# Relay.net
KiCad netlist of a schematic drawn in Altium Designer
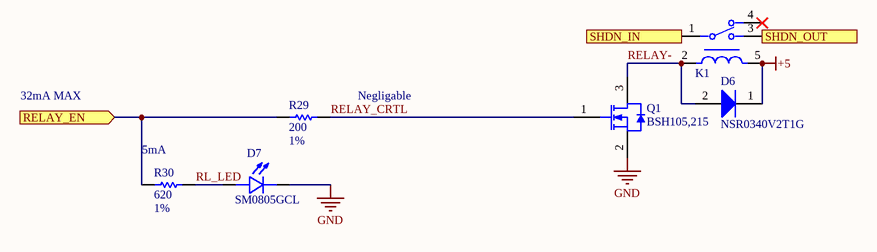
[diagram p0: Relay.SchDoc]

(export (version "E")
  (design (tool "Eeschema 10.0.6"))
  (components
    (comp (ref "D6")
      (value "NSR0340V2T1G")
      (footprint "ONSC-SOD-523-2-502-01_V")
      (description "Schottky Barrier Diode, 2-Pin SOD-523, Pb-Free, Tape and Reel")
      (fields (field (name "MANUFACTURER") "On Semiconductor"))
      (libsource (lib "Altium Content Vault") (part "ONSC-D-K1A2-2"))
    )
    (comp (ref "D7")
      (value "SM0805GCL")
      (footprint "LEDC2012X135N_SM0805GCL(Primary)")
      (description "Green 574nm LED Indication - Discrete 1.9V 0805 (2012 Metric)")
      (libsource (lib "bspd parts") (part "SM0805GCL"))
    )
    (comp (ref "K1")
      (value "Relay_Omron_Electronics_Inc._G5LE-1_DC5_eec")
      (footprint "Omron_Electronics_Inc._G5LE-1_DC5_0")
      (description "RELAY GEN PURPOSE SPDT 10A 5V")
      (fields (field (name "PART NUMBER") "G5LE-1 DC5") (field (name "VOLTAGE") "30V"))
      (libsource (lib "bspd parts") (part "Relay_Omron_Electronics_Inc._G5LE-1_DC5_eec"))
    )
    (comp (ref "Q1")
      (value "BSH105,215")
      (footprint "NXP-SOT23_M")
      (fields (field (name "MANUFACTURER") "NXP Semiconductors"))
      (libsource (lib "Altium Content Vault") (part "NXP-NMOS-GSD-3_B"))
    )
    (comp (ref "R29")
      (value "RES 0603 200 1%")
      (footprint "0603_RES")
      (description "Resistor Surface Mount, 200 Ohms, 0603 Footprint, 1% Tolerance 0.1W")
      (fields
        (field (name "VAL") "200")
        (field (name "TOL") "1%")
        (field (name "MANUFACTURER") "Various")
        (field (name "TOLERANCE") "1%")
      )
      (libsource (lib "Passive Components") (part "res"))
    )
    (comp (ref "R30")
      (value "RES 0603 620 1%")
      (footprint "0603_RES")
      (description "Resistor Surface Mount, 620 Ohms, 0603 Footprint, 1% Tolerance 0.1W")
      (fields
        (field (name "VAL") "620")
        (field (name "TOL") "1%")
        (field (name "MANUFACTURER") "Various")
        (field (name "TOLERANCE") "1%")
      )
      (libsource (lib "Passive Components") (part "res"))
    )
  )
  (nets
    (net (code "1") (name "+5") (class "Default")
      (node (ref "D6") (pin "1") (pinfunction "K_1") (pintype "passive"))
      (node (ref "K1") (pin "5") (pinfunction "5_5") (pintype "passive"))
    )
    (net (code "2") (name "/RELAY-") (class "Default")
      (node (ref "D6") (pin "2") (pinfunction "A_2") (pintype "passive"))
      (node (ref "K1") (pin "2") (pinfunction "2_2") (pintype "passive"))
      (node (ref "Q1") (pin "3") (pinfunction "D_3") (pintype "passive"))
    )
    (net (code "3") (name "/RELAY_CRTL") (class "Default")
      (node (ref "Q1") (pin "1") (pinfunction "G_1") (pintype "passive"))
      (node (ref "R29") (pin "2") (pinfunction "2_2") (pintype "passive"))
    )
    (net (code "4") (name "/RELAY_EN") (class "Default")
      (node (ref "R29") (pin "1") (pinfunction "1_1") (pintype "passive"))
      (node (ref "R30") (pin "1") (pinfunction "1_1") (pintype "passive"))
    )
    (net (code "5") (name "/RL_LED") (class "Default")
      (node (ref "D7") (pin "A") (pinfunction "A_A") (pintype "passive"))
      (node (ref "R30") (pin "2") (pinfunction "2_2") (pintype "passive"))
    )
    (net (code "6") (name "/SHDN_IN") (class "Default")
      (node (ref "K1") (pin "1") (pinfunction "1_1") (pintype "passive"))
    )
    (net (code "7") (name "/SHDN_OUT") (class "Default")
      (node (ref "K1") (pin "3") (pinfunction "3_3") (pintype "passive"))
    )
    (net (code "8") (name "GND") (class "Default")
      (node (ref "D7") (pin "C") (pinfunction "C_C") (pintype "passive"))
      (node (ref "Q1") (pin "2") (pinfunction "S_2") (pintype "passive"))
    )
    (net (code "9") (name "unconnected-(K1-Pad4)") (class "Default")
      (node (ref "K1") (pin "4") (pinfunction "4_4") (pintype "passive+no_connect"))
    )
  )
)
